# schematic.net
KiCad netlist of a schematic drawn in EasyEDA
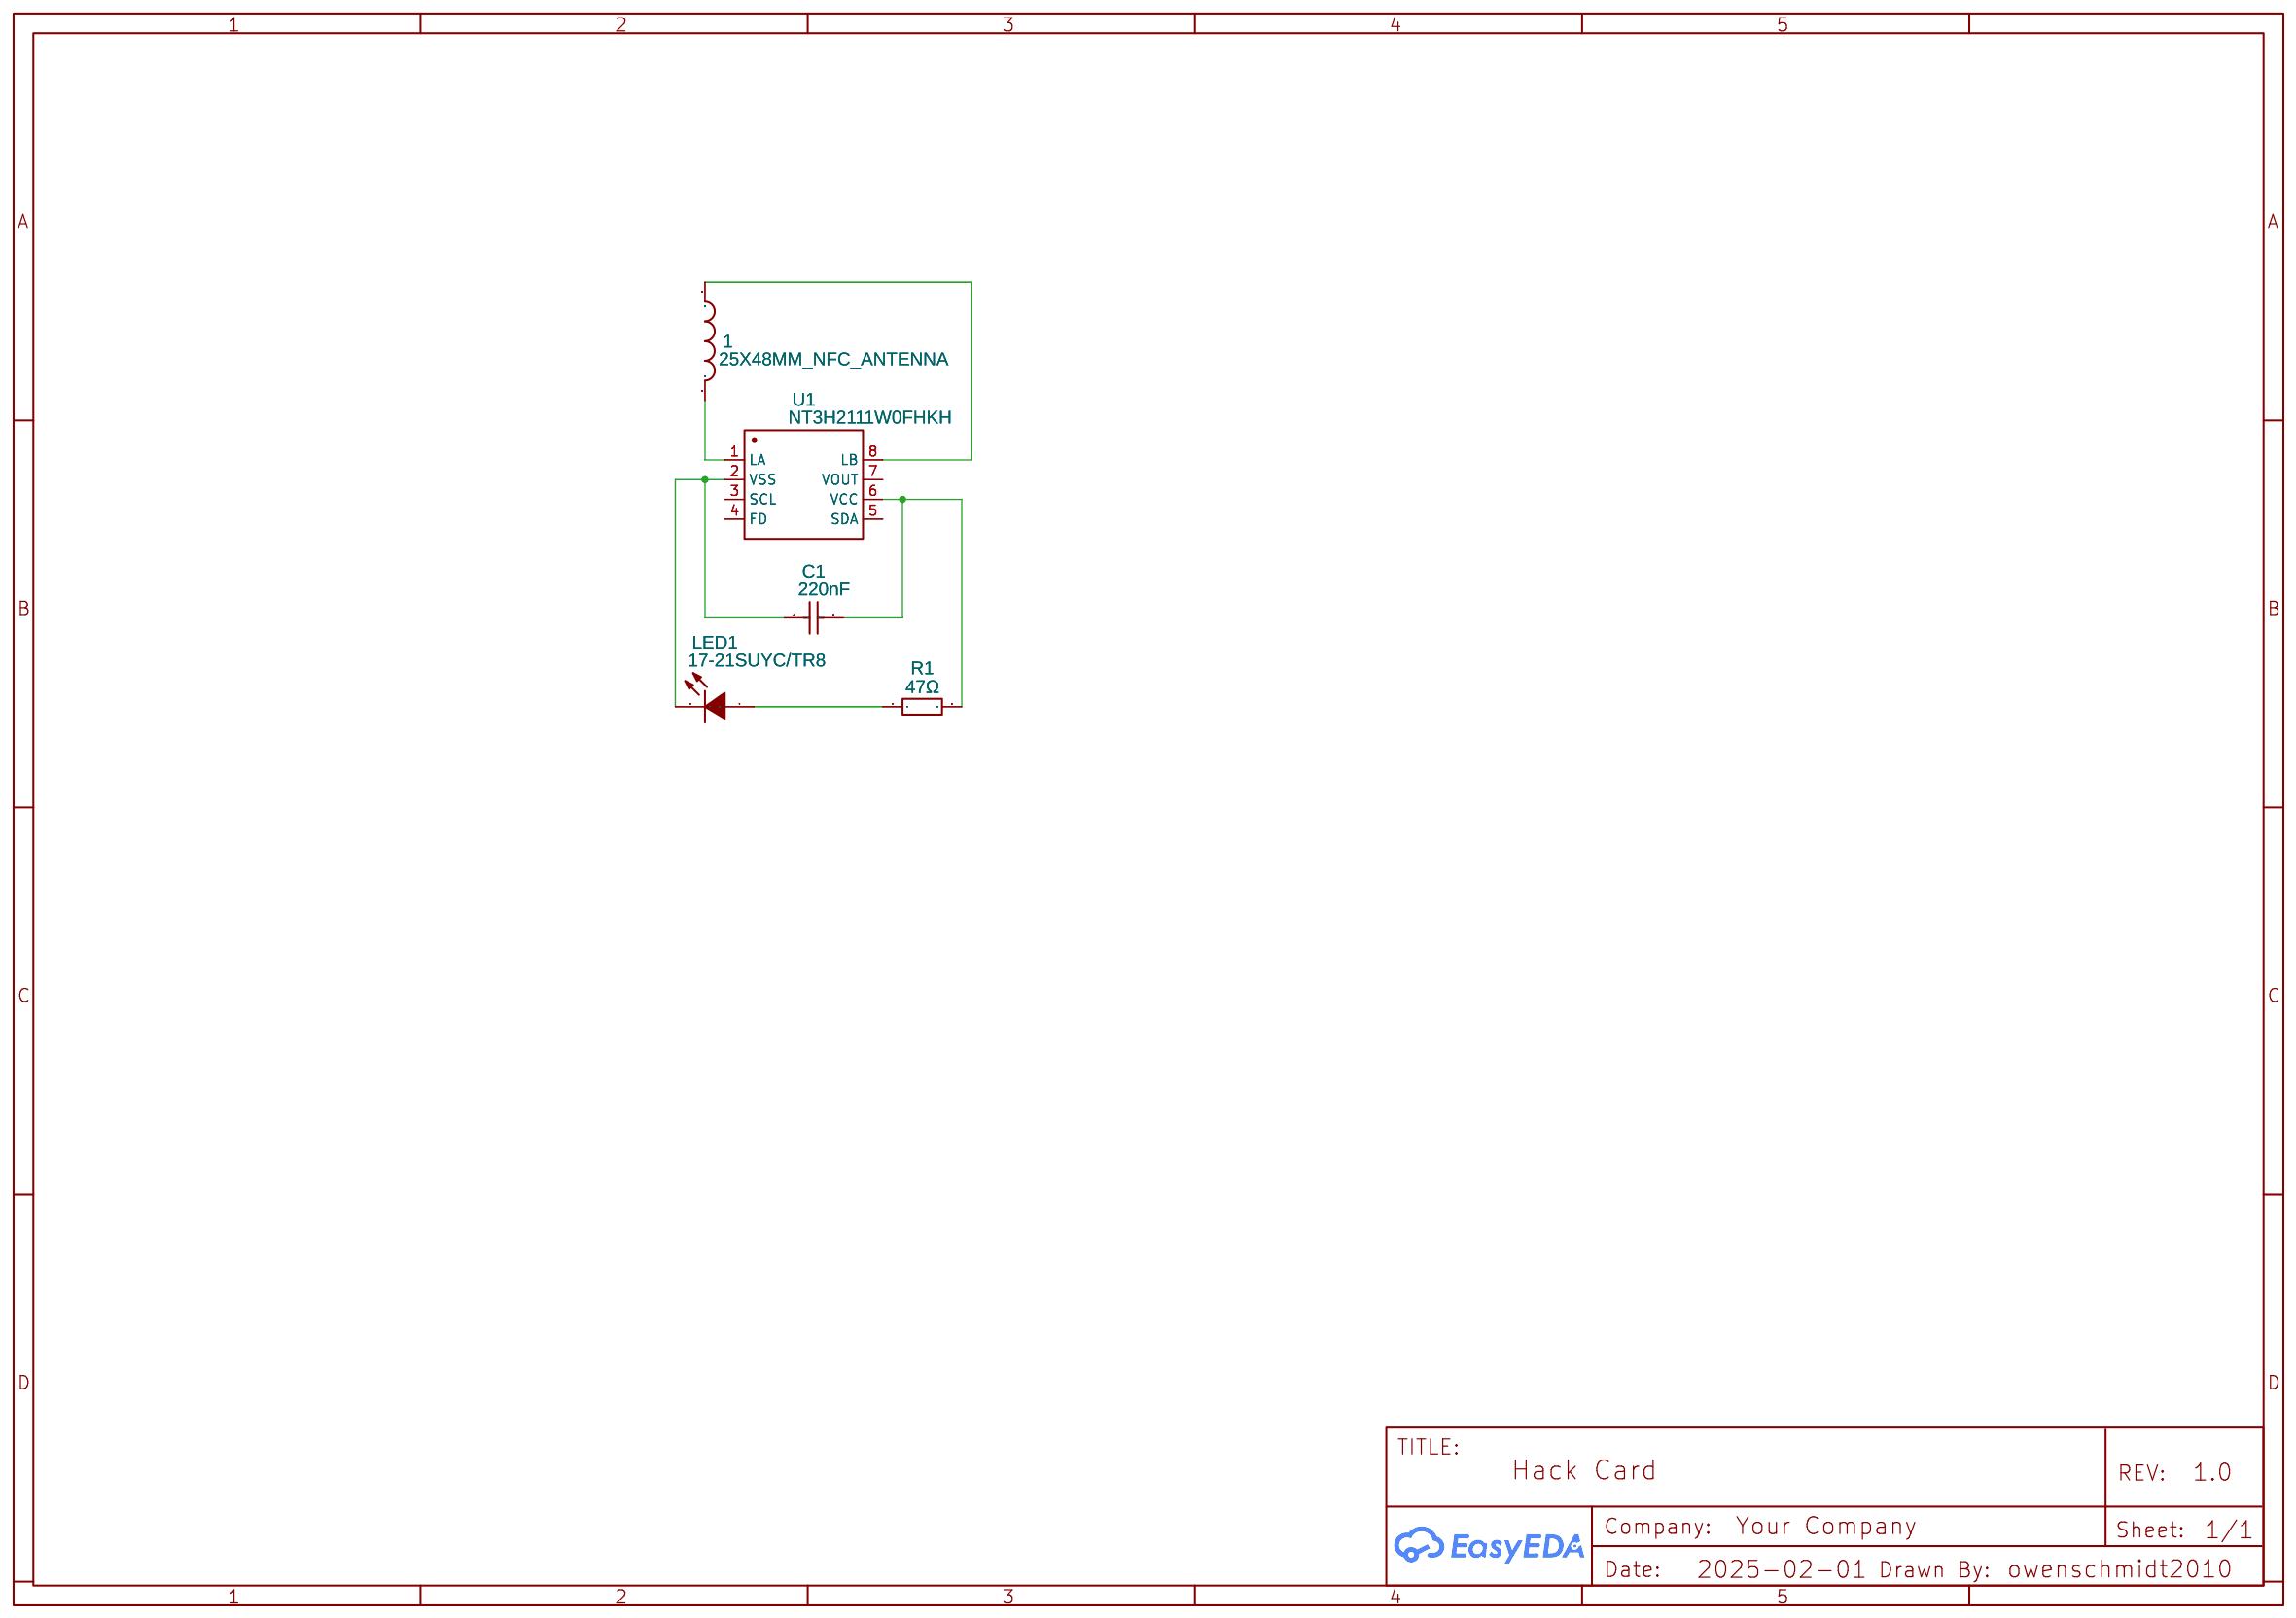
[diagram p0: schematic sheet]

(export (version "E")
  (design (tool "Eeschema 10.0.6"))
  (components
    (comp (ref "1") (value "25X48MM_NFC_ANTENNA") (libsource (lib "") (part "25X48MM_NFC_ANTENNA")))
    (comp (ref "C1")
      (value "220nF")
      (fields
        (field (name "Manufacturer Part") "CL10B224KA8NNNC")
        (field (name "Manufacturer") "SAMSUNG(三星)")
      )
      (libsource (lib "") (part "CL10B224KA8NNNC"))
    )
    (comp (ref "LED1")
      (value "17-21SUYC/TR8")
      (fields (field (name "Manufacturer Part") "KT-0805黄灯") (field (name "Manufacturer") "KENTO"))
      (libsource (lib "") (part "17-21SUYC/TR8"))
    )
    (comp (ref "R1")
      (value "47Ω")
      (fields
        (field (name "Manufacturer Part") "0603WAF470JT5E")
        (field (name "Manufacturer") "UNI-ROYAL(厚声)")
      )
      (libsource (lib "") (part "0603WAF470JT5E"))
    )
    (comp (ref "U1")
      (value "NT3H2111W0FHKH")
      (fields (field (name "Manufacturer") "NXP(恩智浦)"))
      (libsource (lib "") (part "NT3H2111W0FHKH"))
    )
  )
  (nets
    (net (code "1") (name "Net-(LED1-+)") (class "Default")
      (node (ref "LED1") (pin "1") (pinfunction "+_1") (pintype "unspecified"))
      (node (ref "R1") (pin "1") (pinfunction "1_1") (pintype "input"))
    )
    (net (code "2") (name "Net-(LED1--)") (class "Default")
      (node (ref "C1") (pin "1") (pinfunction "1_1") (pintype "input"))
      (node (ref "LED1") (pin "2") (pinfunction "-_2") (pintype "unspecified"))
      (node (ref "U1") (pin "2") (pinfunction "VSS_2") (pintype "unspecified"))
    )
    (net (code "3") (name "Net-(U1-LA)") (class "Default")
      (node (ref "1") (pin "P$2") (pinfunction "P$2_P$2") (pintype "bidirectional"))
      (node (ref "U1") (pin "1") (pinfunction "LA_1") (pintype "unspecified"))
    )
    (net (code "4") (name "Net-(U1-LB)") (class "Default")
      (node (ref "1") (pin "P$1") (pinfunction "P$1_P$1") (pintype "bidirectional"))
      (node (ref "U1") (pin "8") (pinfunction "LB_8") (pintype "unspecified"))
    )
    (net (code "5") (name "Net-(U1-VCC)") (class "Default")
      (node (ref "C1") (pin "2") (pinfunction "2_2") (pintype "input"))
      (node (ref "R1") (pin "2") (pinfunction "2_2") (pintype "input"))
      (node (ref "U1") (pin "6") (pinfunction "VCC_6") (pintype "unspecified"))
    )
    (net (code "6") (name "unconnected-(U1-FD-Pad4)") (class "Default")
      (node (ref "U1") (pin "4") (pinfunction "FD_4") (pintype "unspecified"))
    )
    (net (code "7") (name "unconnected-(U1-SCL-Pad3)") (class "Default")
      (node (ref "U1") (pin "3") (pinfunction "SCL_3") (pintype "unspecified"))
    )
    (net (code "8") (name "unconnected-(U1-SDA-Pad5)") (class "Default")
      (node (ref "U1") (pin "5") (pinfunction "SDA_5") (pintype "unspecified"))
    )
    (net (code "9") (name "unconnected-(U1-VOUT-Pad7)") (class "Default")
      (node (ref "U1") (pin "7") (pinfunction "VOUT_7") (pintype "unspecified"))
    )
  )
)
